# 04.net
KiCad netlist of a schematic drawn in Altium Designer
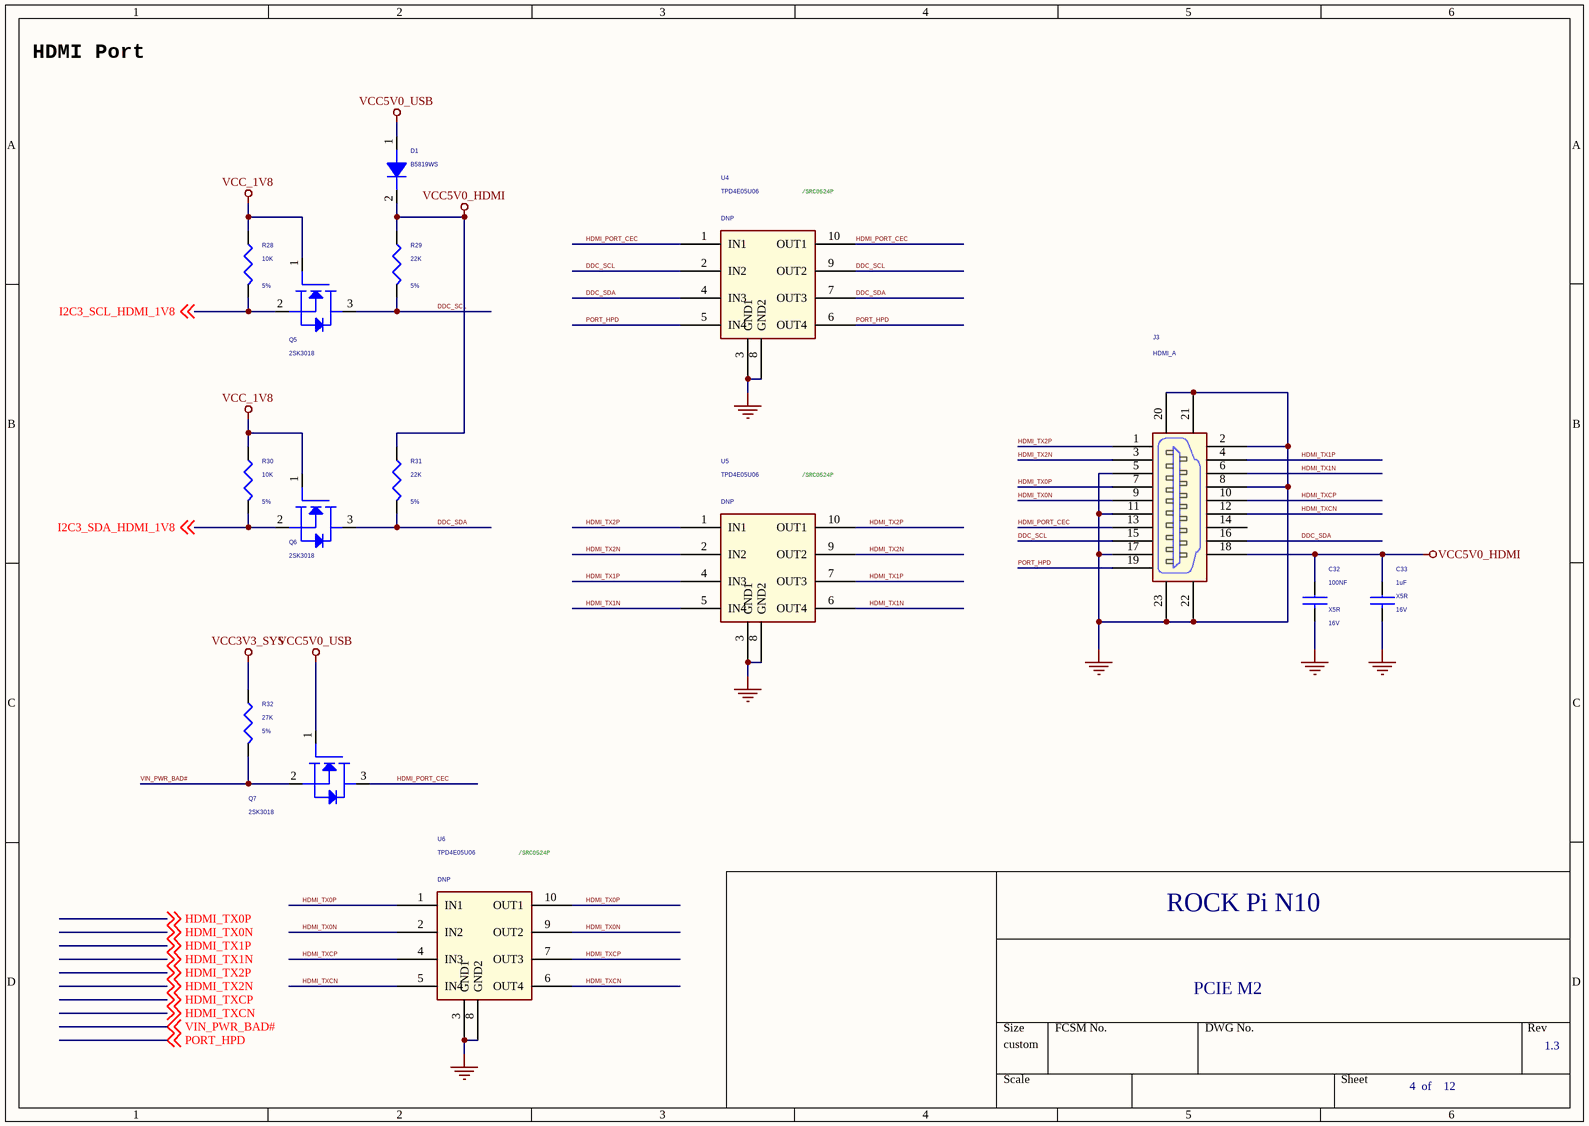
[diagram p0: 04.SchDoc]

(export (version "E")
  (design (tool "Eeschema 10.0.6"))
  (components
    (comp (ref "C32")
      (value "100NF")
      (footprint "C0402")
      (description "cap,100.00nF,+/-10%,16V,X5R,C0402")
      (fields
        (field (name "DIELECTRIC") "X5R")
        (field (name "VOLTAGE") "16V")
        (field (name "TOLERANCE") "10%")
        (field (name "MANUFACTURER") "TDK")
        (field (name "CREATED BY") "JJJ")
      )
      (libsource (lib "*") (part "CAP NP_2"))
    )
    (comp (ref "C33")
      (value "1uF")
      (footprint "C0402")
      (description "cap,1.00uF,+/-10%,16V,X5R,C0402")
      (fields
        (field (name "DIELECTRIC") "X5R")
        (field (name "VOLTAGE") "16V")
        (field (name "MANUFACTURER") "TDK")
        (field (name "TOLERANCE") "10%")
        (field (name "CREATED BY") "JJJ")
      )
      (libsource (lib "*") (part "CAP NP_2"))
    )
    (comp (ref "D1")
      (value "B5819WS")
      (footprint "SOD_323")
      (description "Schottky Barrier，B5819WS SOD-323")
      (fields (field (name "MANUFACTURER") "长电") (field (name "CREATED BY") "JJJ"))
      (libsource (lib "*") (part "DIODE_Dup2"))
    )
    (comp (ref "J3")
      (value "HDMI_A")
      (footprint "HDMIA19_HDMI_01A")
      (description "通用A型HDMI座,卧式,侧插")
      (fields (field (name "MANUFACTURER") "旺科达") (field (name "CREATED BY") "JJJ"))
      (libsource (lib "*") (part "HDMI_A"))
    )
    (comp (ref "Q5")
      (value "2SK3018")
      (footprint "SOT23")
      (description "NMOS,2SK3018,SOT_323,Id=0.1A,Vds=30V")
      (fields (field (name "MANUFACTURER") "ROHM") (field (name "CREATED BY") "JJJ"))
      (libsource (lib "*") (part "MOSFET N"))
    )
    (comp (ref "Q6")
      (value "2SK3018")
      (footprint "SOT23")
      (description "NMOS,2SK3018,SOT_323,Id=0.1A,Vds=30V")
      (fields (field (name "MANUFACTURER") "ROHM") (field (name "CREATED BY") "JJJ"))
      (libsource (lib "*") (part "MOSFET N"))
    )
    (comp (ref "Q7")
      (value "2SK3018")
      (footprint "SOT23")
      (description "NMOS,2SK3018,SOT_323,Id=0.1A,Vds=30V")
      (fields (field (name "MANUFACTURER") "ROHM") (field (name "CREATED BY") "JJJ"))
      (libsource (lib "*") (part "MOSFET N"))
    )
    (comp (ref "R28")
      (value "10K")
      (footprint "R0402")
      (description "通用厚膜电阻,10K,+/-5%,R0402,1/16W.")
      (fields
        (field (name "TOLERANCE") "5%")
        (field (name "MANUFACTURER") "YAGEO")
        (field (name "CREATED BY") "YTL")
      )
      (libsource (lib "*") (part "RESISTOR_3"))
    )
    (comp (ref "R29")
      (value "22K")
      (footprint "R0402")
      (description "通用厚膜电阻,1K5,+/-5%,R0402,1/16W.")
      (fields
        (field (name "TOLERANCE") "5%")
        (field (name "MANUFACTURER") "YAGEO")
        (field (name "CREATED BY") "YTL")
      )
      (libsource (lib "*") (part "RESISTOR_3"))
    )
    (comp (ref "R30")
      (value "10K")
      (footprint "R0402")
      (description "通用厚膜电阻,10K,+/-5%,R0402,1/16W.")
      (fields
        (field (name "TOLERANCE") "5%")
        (field (name "MANUFACTURER") "YAGEO")
        (field (name "CREATED BY") "YTL")
      )
      (libsource (lib "*") (part "RESISTOR_3"))
    )
    (comp (ref "R31")
      (value "22K")
      (footprint "R0402")
      (description "通用厚膜电阻,1K5,+/-5%,R0402,1/16W.")
      (fields
        (field (name "TOLERANCE") "5%")
        (field (name "MANUFACTURER") "YAGEO")
        (field (name "CREATED BY") "YTL")
      )
      (libsource (lib "*") (part "RESISTOR_3"))
    )
    (comp (ref "R32")
      (value "27K")
      (footprint "R0402")
      (description "通用厚膜电阻,27K,+/-5%,R0402,1/16W.")
      (fields
        (field (name "TOLERANCE") "5%")
        (field (name "MANUFACTURER") "YAGEO")
        (field (name "CREATED BY") "YTL")
      )
      (libsource (lib "*") (part "RESISTOR_3"))
    )
    (comp (ref "U4")
      (value "TPD4E05U06")
      (footprint "SON10_2R50X1R00X0R50")
      (description "unidirectional ESD protection devices with ultra low capacitance")
      (fields
        (field (name "OPTION") "DNP")
        (field (name "MANUFACTURER") "TI（德州仪器）")
        (field (name "CREATED BY") "JJJ")
      )
      (libsource (lib "*") (part "ESD_TPD4E05U06"))
    )
    (comp (ref "U5")
      (value "TPD4E05U06")
      (footprint "SON10_2R50X1R00X0R50")
      (description "unidirectional ESD protection devices with ultra low capacitance")
      (fields
        (field (name "MANUFACTURER") "TI（德州仪器）")
        (field (name "OPTION") "DNP")
        (field (name "CREATED BY") "JJJ")
      )
      (libsource (lib "*") (part "ESD_TPD4E05U06"))
    )
    (comp (ref "U6")
      (value "TPD4E05U06")
      (footprint "SON10_2R50X1R00X0R50")
      (description "unidirectional ESD protection devices with ultra low capacitance")
      (fields
        (field (name "MANUFACTURER") "TI（德州仪器）")
        (field (name "OPTION") "DNP")
        (field (name "CREATED BY") "JJJ")
      )
      (libsource (lib "*") (part "ESD_TPD4E05U06"))
    )
  )
  (nets
    (net (code "1") (name "/DDC_SCL") (class "Default")
      (node (ref "J3") (pin "15") (pinfunction "15_15") (pintype "passive"))
      (node (ref "Q5") (pin "3") (pinfunction "DRAIN_3") (pintype "passive"))
      (node (ref "R29") (pin "2") (pinfunction "2_2") (pintype "passive"))
      (node (ref "U4") (pin "2") (pinfunction "IN2_2") (pintype "passive"))
      (node (ref "U4") (pin "9") (pinfunction "OUT2_9") (pintype "passive"))
    )
    (net (code "2") (name "/DDC_SDA") (class "Default")
      (node (ref "J3") (pin "16") (pinfunction "16_16") (pintype "passive"))
      (node (ref "Q6") (pin "3") (pinfunction "DRAIN_3") (pintype "passive"))
      (node (ref "R31") (pin "2") (pinfunction "2_2") (pintype "passive"))
      (node (ref "U4") (pin "4") (pinfunction "IN3_4") (pintype "passive"))
      (node (ref "U4") (pin "7") (pinfunction "OUT3_7") (pintype "passive"))
    )
    (net (code "3") (name "/HDMI_PORT_CEC") (class "Default")
      (node (ref "J3") (pin "13") (pinfunction "13_13") (pintype "passive"))
      (node (ref "Q7") (pin "3") (pinfunction "DRAIN_3") (pintype "passive"))
      (node (ref "U4") (pin "1") (pinfunction "IN1_1") (pintype "passive"))
      (node (ref "U4") (pin "10") (pinfunction "OUT1_10") (pintype "passive"))
    )
    (net (code "4") (name "GND") (class "Default")
      (node (ref "C32") (pin "2") (pinfunction "2_2") (pintype "passive"))
      (node (ref "C33") (pin "2") (pinfunction "2_2") (pintype "passive"))
      (node (ref "J3") (pin "11") (pinfunction "11_11") (pintype "passive"))
      (node (ref "J3") (pin "17") (pinfunction "17_17") (pintype "passive"))
      (node (ref "J3") (pin "2") (pinfunction "2_2") (pintype "passive"))
      (node (ref "J3") (pin "20") (pinfunction "20_20") (pintype "passive"))
      (node (ref "J3") (pin "21") (pinfunction "21_21") (pintype "passive"))
      (node (ref "J3") (pin "22") (pinfunction "22_22") (pintype "passive"))
      (node (ref "J3") (pin "23") (pinfunction "23_23") (pintype "passive"))
      (node (ref "J3") (pin "5") (pinfunction "5_5") (pintype "passive"))
      (node (ref "J3") (pin "8") (pinfunction "8_8") (pintype "passive"))
      (node (ref "U4") (pin "3") (pinfunction "GND1_3") (pintype "passive"))
      (node (ref "U4") (pin "8") (pinfunction "GND2_8") (pintype "passive"))
      (node (ref "U5") (pin "3") (pinfunction "GND1_3") (pintype "passive"))
      (node (ref "U5") (pin "8") (pinfunction "GND2_8") (pintype "passive"))
      (node (ref "U6") (pin "3") (pinfunction "GND1_3") (pintype "passive"))
      (node (ref "U6") (pin "8") (pinfunction "GND2_8") (pintype "passive"))
    )
    (net (code "5") (name "HDMI_TX0N") (class "Default")
      (node (ref "J3") (pin "9") (pinfunction "9_9") (pintype "passive"))
      (node (ref "U6") (pin "2") (pinfunction "IN2_2") (pintype "passive"))
      (node (ref "U6") (pin "9") (pinfunction "OUT2_9") (pintype "passive"))
    )
    (net (code "6") (name "HDMI_TX0P") (class "Default")
      (node (ref "J3") (pin "7") (pinfunction "7_7") (pintype "passive"))
      (node (ref "U6") (pin "1") (pinfunction "IN1_1") (pintype "passive"))
      (node (ref "U6") (pin "10") (pinfunction "OUT1_10") (pintype "passive"))
    )
    (net (code "7") (name "HDMI_TX1N") (class "Default")
      (node (ref "J3") (pin "6") (pinfunction "6_6") (pintype "passive"))
      (node (ref "U5") (pin "5") (pinfunction "IN4_5") (pintype "passive"))
      (node (ref "U5") (pin "6") (pinfunction "OUT4_6") (pintype "passive"))
    )
    (net (code "8") (name "HDMI_TX1P") (class "Default")
      (node (ref "J3") (pin "4") (pinfunction "4_4") (pintype "passive"))
      (node (ref "U5") (pin "4") (pinfunction "IN3_4") (pintype "passive"))
      (node (ref "U5") (pin "7") (pinfunction "OUT3_7") (pintype "passive"))
    )
    (net (code "9") (name "HDMI_TX2N") (class "Default")
      (node (ref "J3") (pin "3") (pinfunction "3_3") (pintype "passive"))
      (node (ref "U5") (pin "2") (pinfunction "IN2_2") (pintype "passive"))
      (node (ref "U5") (pin "9") (pinfunction "OUT2_9") (pintype "passive"))
    )
    (net (code "10") (name "HDMI_TX2P") (class "Default")
      (node (ref "J3") (pin "1") (pinfunction "$PIN0_1") (pintype "passive"))
      (node (ref "U5") (pin "1") (pinfunction "IN1_1") (pintype "passive"))
      (node (ref "U5") (pin "10") (pinfunction "OUT1_10") (pintype "passive"))
    )
    (net (code "11") (name "HDMI_TXCN") (class "Default")
      (node (ref "J3") (pin "12") (pinfunction "12_12") (pintype "passive"))
      (node (ref "U6") (pin "5") (pinfunction "IN4_5") (pintype "passive"))
      (node (ref "U6") (pin "6") (pinfunction "OUT4_6") (pintype "passive"))
    )
    (net (code "12") (name "HDMI_TXCP") (class "Default")
      (node (ref "J3") (pin "10") (pinfunction "10_10") (pintype "passive"))
      (node (ref "U6") (pin "4") (pinfunction "IN3_4") (pintype "passive"))
      (node (ref "U6") (pin "7") (pinfunction "OUT3_7") (pintype "passive"))
    )
    (net (code "13") (name "I2C3_SCL_HDMI_1V8") (class "Default")
      (node (ref "Q5") (pin "2") (pinfunction "SOURCE_2") (pintype "passive"))
      (node (ref "R28") (pin "2") (pinfunction "2_2") (pintype "passive"))
    )
    (net (code "14") (name "I2C3_SDA_HDMI_1V8") (class "Default")
      (node (ref "Q6") (pin "2") (pinfunction "SOURCE_2") (pintype "passive"))
      (node (ref "R30") (pin "2") (pinfunction "2_2") (pintype "passive"))
    )
    (net (code "15") (name "PORT_HPD") (class "Default")
      (node (ref "J3") (pin "19") (pinfunction "19_19") (pintype "passive"))
      (node (ref "U4") (pin "5") (pinfunction "IN4_5") (pintype "passive"))
      (node (ref "U4") (pin "6") (pinfunction "OUT4_6") (pintype "passive"))
    )
    (net (code "16") (name "VCC3V3_SYS") (class "Default")
      (node (ref "R32") (pin "1") (pinfunction "1_1") (pintype "passive"))
    )
    (net (code "17") (name "VCC5V0_HDMI") (class "Default")
      (node (ref "C32") (pin "1") (pinfunction "1_1") (pintype "passive"))
      (node (ref "C33") (pin "1") (pinfunction "1_1") (pintype "passive"))
      (node (ref "D1") (pin "2") (pinfunction "K_2") (pintype "passive"))
      (node (ref "J3") (pin "18") (pinfunction "18_18") (pintype "passive"))
      (node (ref "R29") (pin "1") (pinfunction "1_1") (pintype "passive"))
      (node (ref "R31") (pin "1") (pinfunction "1_1") (pintype "passive"))
    )
    (net (code "18") (name "VCC5V0_USB") (class "Default")
      (node (ref "D1") (pin "1") (pinfunction "A_1") (pintype "passive"))
      (node (ref "Q7") (pin "1") (pinfunction "GATE_1") (pintype "passive"))
    )
    (net (code "19") (name "VCC_1V8") (class "Default")
      (node (ref "Q5") (pin "1") (pinfunction "GATE_1") (pintype "passive"))
      (node (ref "Q6") (pin "1") (pinfunction "GATE_1") (pintype "passive"))
      (node (ref "R28") (pin "1") (pinfunction "1_1") (pintype "passive"))
      (node (ref "R30") (pin "1") (pinfunction "1_1") (pintype "passive"))
    )
    (net (code "20") (name "VIN_PWR_BAD#") (class "Default")
      (node (ref "Q7") (pin "2") (pinfunction "SOURCE_2") (pintype "passive"))
      (node (ref "R32") (pin "2") (pinfunction "2_2") (pintype "passive"))
    )
    (net (code "21") (name "unconnected-(J3-Pad14)") (class "Default")
      (node (ref "J3") (pin "14") (pinfunction "14_14") (pintype "passive"))
    )
  )
)
